# design.net
KiCad netlist of a schematic drawn in Altium Designer
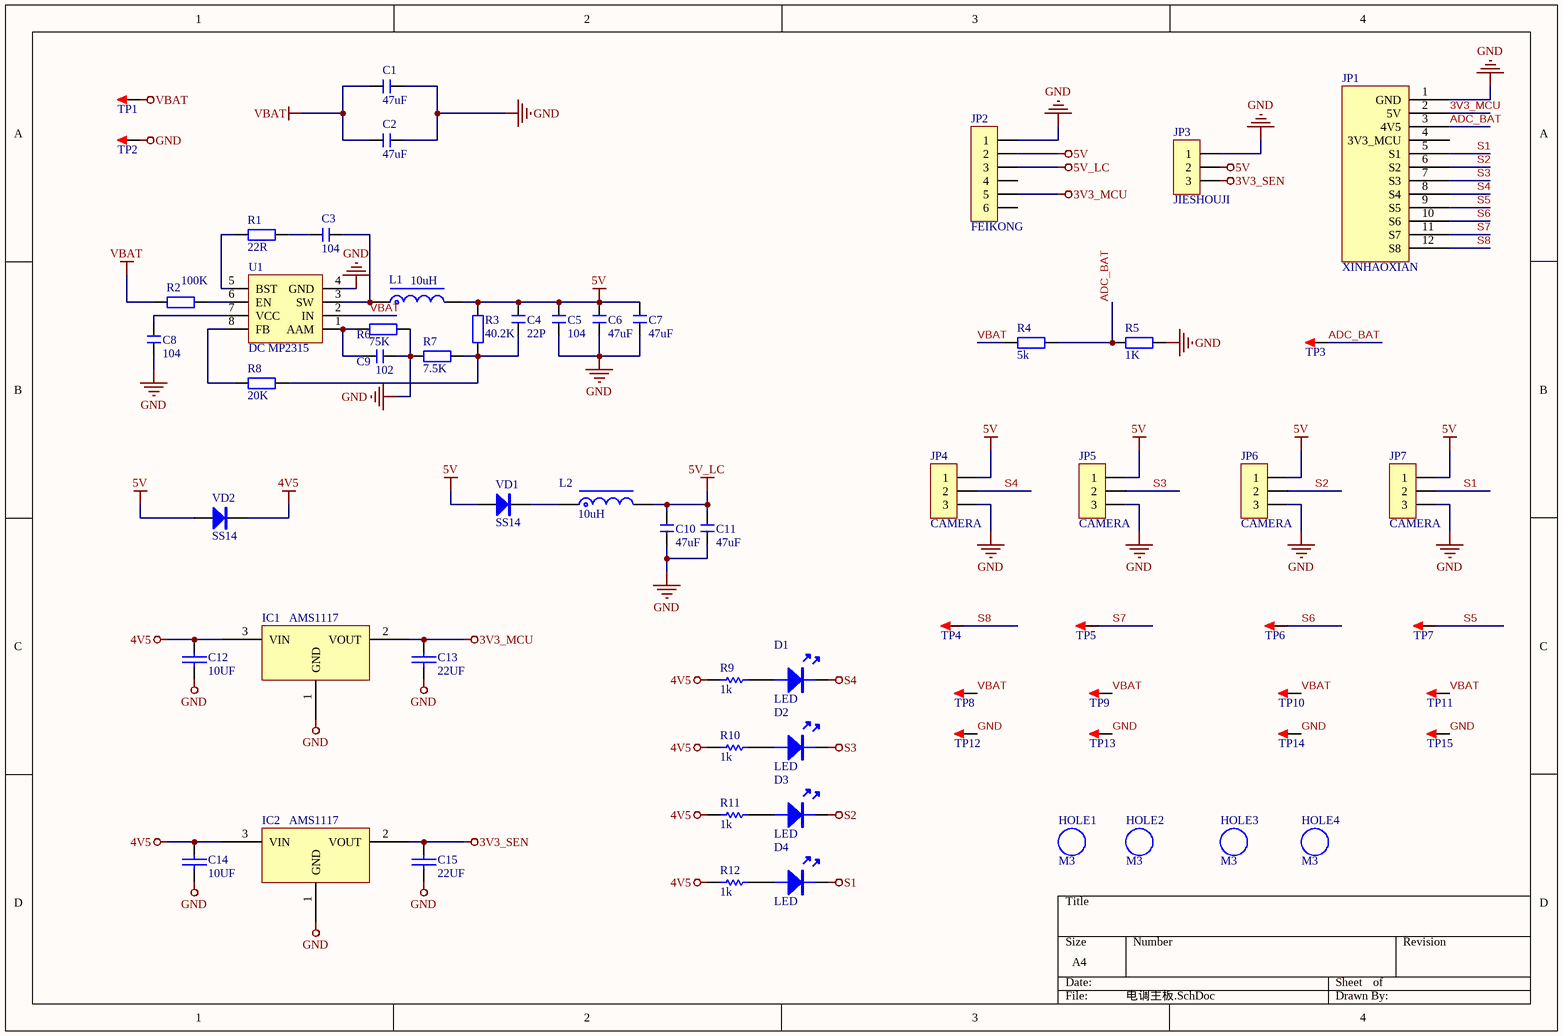
[diagram p0: 电调主板.SchDoc]

(export (version "E")
  (design (tool "Eeschema 10.0.6"))
  (components
    (comp (ref "C1")
      (value "47uF")
      (footprint "0603C")
      (description "无极性贴片电容")
      (fields (field (name "版权归属") "源创客"))
      (libsource (lib "ATKF405 V1.1") (part "C"))
    )
    (comp (ref "C2")
      (value "47uF")
      (footprint "0603C")
      (description "无极性贴片电容")
      (fields (field (name "版权归属") "源创客"))
      (libsource (lib "ATKF405 V1.1") (part "C"))
    )
    (comp (ref "C3")
      (value "104")
      (footprint "0603C")
      (description "无极性贴片电容")
      (fields (field (name "版权归属") "源创客"))
      (libsource (lib "ATKF405 V1.1") (part "C"))
    )
    (comp (ref "C4")
      (value "22P")
      (footprint "0603C")
      (description "无极性贴片电容")
      (fields (field (name "版权归属") "源创客"))
      (libsource (lib "ATKF405 V1.1") (part "C"))
    )
    (comp (ref "C5")
      (value "104")
      (footprint "0603C")
      (description "无极性贴片电容")
      (fields (field (name "版权归属") "源创客"))
      (libsource (lib "ATKF405 V1.1") (part "C"))
    )
    (comp (ref "C6")
      (value "47uF")
      (footprint "0603C")
      (description "无极性贴片电容")
      (fields (field (name "版权归属") "源创客"))
      (libsource (lib "ATKF405 V1.1") (part "C"))
    )
    (comp (ref "C7")
      (value "47uF")
      (footprint "0603C")
      (description "无极性贴片电容")
      (fields (field (name "版权归属") "源创客"))
      (libsource (lib "ATKF405 V1.1") (part "C"))
    )
    (comp (ref "C8")
      (value "104")
      (footprint "0603C")
      (description "无极性贴片电容")
      (fields (field (name "版权归属") "源创客"))
      (libsource (lib "ATKF405 V1.1") (part "C"))
    )
    (comp (ref "C9")
      (value "102")
      (footprint "0603C")
      (description "无极性贴片电容")
      (fields (field (name "版权归属") "源创客"))
      (libsource (lib "ATKF405 V1.1") (part "C"))
    )
    (comp (ref "C10")
      (value "47uF")
      (footprint "0603C")
      (description "无极性贴片电容")
      (fields (field (name "版权归属") "源创客"))
      (libsource (lib "ATKF405 V1.1") (part "C"))
    )
    (comp (ref "C11")
      (value "47uF")
      (footprint "0603C")
      (description "无极性贴片电容")
      (fields (field (name "版权归属") "源创客"))
      (libsource (lib "ATKF405 V1.1") (part "C"))
    )
    (comp (ref "C12")
      (value "10UF")
      (footprint "0603C")
      (description "无极性电容")
      (libsource (lib "电容") (part "CAP"))
    )
    (comp (ref "C13")
      (value "22UF")
      (footprint "0603C")
      (description "无极性电容")
      (libsource (lib "电容") (part "CAP"))
    )
    (comp (ref "C14")
      (value "10UF")
      (footprint "0603C")
      (description "无极性电容")
      (libsource (lib "电容") (part "CAP"))
    )
    (comp (ref "C15")
      (value "22UF")
      (footprint "0603C")
      (description "无极性电容")
      (libsource (lib "电容") (part "CAP"))
    )
    (comp (ref "D1") (value "LED") (footprint "LED-0603G") (libsource (lib "LED") (part "LED")))
    (comp (ref "D2") (value "LED") (footprint "LED-0603G") (libsource (lib "LED") (part "LED")))
    (comp (ref "D3") (value "LED") (footprint "LED-0603G") (libsource (lib "LED") (part "LED")))
    (comp (ref "D4") (value "LED") (footprint "LED-0603G") (libsource (lib "LED") (part "LED")))
    (comp (ref "HOLE1")
      (value "M3")
      (footprint "M3 5.4MM")
      (description "铜柱孔")
      (fields (field (name "版权归属") "源创客"))
      (libsource (lib "STM32F407_CORE_BOARD") (part "M3"))
    )
    (comp (ref "HOLE2")
      (value "M3")
      (footprint "M3 5.4MM")
      (description "铜柱孔")
      (fields (field (name "版权归属") "源创客"))
      (libsource (lib "STM32F407_CORE_BOARD") (part "M3"))
    )
    (comp (ref "HOLE3")
      (value "M3")
      (footprint "M3 5.4MM")
      (description "铜柱孔")
      (fields (field (name "版权归属") "源创客"))
      (libsource (lib "STM32F407_CORE_BOARD") (part "M3"))
    )
    (comp (ref "HOLE4")
      (value "M3")
      (footprint "M3 5.4MM")
      (description "铜柱孔")
      (fields (field (name "版权归属") "源创客"))
      (libsource (lib "STM32F407_CORE_BOARD") (part "M3"))
    )
    (comp (ref "IC1")
      (value "AMS1117")
      (footprint "AMS1117")
      (description "3V3降压芯片")
      (libsource (lib "飞控主板") (part "AMS1117"))
    )
    (comp (ref "IC2")
      (value "AMS1117")
      (footprint "AMS1117")
      (description "3V3降压芯片")
      (libsource (lib "飞控主板") (part "AMS1117"))
    )
    (comp (ref "JP1")
      (value "XINHAOXIAN")
      (footprint "Headr14")
      (description "14PIN接插件")
      (libsource (lib "飞控主板") (part "Header14"))
    )
    (comp (ref "JP2")
      (value "FEIKONG")
      (footprint "SH1.0 S-W-6P")
      (description "6P接插件")
      (fields (field (name "版权归属") "源创客"))
      (libsource (lib "ATKF405 V1.1") (part "Header 6"))
    )
    (comp (ref "JP3")
      (value "JIESHOUJI")
      (footprint "MX 1.25-WS-3P")
      (description "3P接插件")
      (fields (field (name "版权归属") "源创客"))
      (libsource (lib "ATKF405 V1.1") (part "Header 3"))
    )
    (comp (ref "JP4")
      (value "CAMERA")
      (footprint "MX 1.25-WS-3P")
      (description "3P接插件")
      (fields (field (name "版权归属") "源创客"))
      (libsource (lib "ATKF405 V1.1") (part "Header 3"))
    )
    (comp (ref "JP5")
      (value "CAMERA")
      (footprint "MX 1.25-WS-3P")
      (description "3P接插件")
      (fields (field (name "版权归属") "源创客"))
      (libsource (lib "ATKF405 V1.1") (part "Header 3"))
    )
    (comp (ref "JP6")
      (value "CAMERA")
      (footprint "MX 1.25-WS-3P")
      (description "3P接插件")
      (fields (field (name "版权归属") "源创客"))
      (libsource (lib "ATKF405 V1.1") (part "Header 3"))
    )
    (comp (ref "JP7")
      (value "CAMERA")
      (footprint "MX 1.25-WS-3P")
      (description "3P接插件")
      (fields (field (name "版权归属") "源创客"))
      (libsource (lib "ATKF405 V1.1") (part "Header 3"))
    )
    (comp (ref "L1")
      (value "10uH")
      (footprint "L-SMD-0420")
      (description "功率屏蔽电感")
      (fields (field (name "版权归属") "源创客"))
      (libsource (lib "ATKF405 V1.1") (part "L-CDRH"))
    )
    (comp (ref "L2")
      (value "10uH")
      (footprint "NR3015")
      (description "NR功率电感")
      (fields (field (name "版权归属") "源创客"))
      (libsource (lib "ATKF405 V1.1") (part "L-NR"))
    )
    (comp (ref "R1")
      (value "22R")
      (footprint "0805R")
      (description "贴片电阻")
      (fields (field (name "版权归属") "源创客"))
      (libsource (lib "ATKF405 V1.1") (part "R"))
    )
    (comp (ref "R2")
      (value "100K")
      (footprint "0805R")
      (description "贴片电阻")
      (fields (field (name "版权归属") "源创客"))
      (libsource (lib "ATKF405 V1.1") (part "R"))
    )
    (comp (ref "R3")
      (value "40.2K")
      (footprint "0805R")
      (description "贴片电阻")
      (fields (field (name "版权归属") "源创客"))
      (libsource (lib "ATKF405 V1.1") (part "R"))
    )
    (comp (ref "R4")
      (value "5k")
      (footprint "0805R")
      (description "贴片电阻")
      (fields (field (name "版权归属") "源创客"))
      (libsource (lib "ATKF405 V1.1") (part "R"))
    )
    (comp (ref "R5")
      (value "1K")
      (footprint "0805R")
      (description "贴片电阻")
      (fields (field (name "版权归属") "源创客"))
      (libsource (lib "ATKF405 V1.1") (part "R"))
    )
    (comp (ref "R6")
      (value "75K")
      (footprint "0805R")
      (description "贴片电阻")
      (fields (field (name "版权归属") "源创客"))
      (libsource (lib "ATKF405 V1.1") (part "R"))
    )
    (comp (ref "R7")
      (value "7.5K")
      (footprint "0805R")
      (description "贴片电阻")
      (fields (field (name "版权归属") "源创客"))
      (libsource (lib "ATKF405 V1.1") (part "R"))
    )
    (comp (ref "R8")
      (value "20K")
      (footprint "0805R")
      (description "贴片电阻")
      (fields (field (name "版权归属") "源创客"))
      (libsource (lib "ATKF405 V1.1") (part "R"))
    )
    (comp (ref "R9") (value "1k") (footprint "0805R") (libsource (lib "电阻") (part "RES")))
    (comp (ref "R10") (value "1k") (footprint "0805R") (libsource (lib "电阻") (part "RES")))
    (comp (ref "R11") (value "1k") (footprint "0805R") (libsource (lib "电阻") (part "RES")))
    (comp (ref "R12") (value "1k") (footprint "0805R") (libsource (lib "电阻") (part "RES")))
    (comp (ref "TP1")
      (value "TEST")
      (footprint "TEST PAD 1.8")
      (description "测试点")
      (fields (field (name "版权归属") "源创客"))
      (libsource (lib "ATKF405 V1.1") (part "TEST"))
    )
    (comp (ref "TP2")
      (value "TEST")
      (footprint "TEST PAD 1.8")
      (description "测试点")
      (fields (field (name "版权归属") "源创客"))
      (libsource (lib "ATKF405 V1.1") (part "TEST"))
    )
    (comp (ref "TP3")
      (value "TEST")
      (footprint "TEST PAD 1.8")
      (description "测试点")
      (fields (field (name "版权归属") "源创客"))
      (libsource (lib "ATKF405 V1.1") (part "TEST"))
    )
    (comp (ref "TP4")
      (value "TEST")
      (footprint "TEST PAD 1.8")
      (description "测试点")
      (fields (field (name "版权归属") "源创客"))
      (libsource (lib "ATKF405 V1.1") (part "TEST"))
    )
    (comp (ref "TP5")
      (value "TEST")
      (footprint "TEST PAD 1.8")
      (description "测试点")
      (fields (field (name "版权归属") "源创客"))
      (libsource (lib "ATKF405 V1.1") (part "TEST"))
    )
    (comp (ref "TP6")
      (value "TEST")
      (footprint "TEST PAD 1.8")
      (description "测试点")
      (fields (field (name "版权归属") "源创客"))
      (libsource (lib "ATKF405 V1.1") (part "TEST"))
    )
    (comp (ref "TP7")
      (value "TEST")
      (footprint "TEST PAD 1.8")
      (description "测试点")
      (fields (field (name "版权归属") "源创客"))
      (libsource (lib "ATKF405 V1.1") (part "TEST"))
    )
    (comp (ref "TP8")
      (value "TEST")
      (footprint "TEST PAD 1.8")
      (description "测试点")
      (fields (field (name "版权归属") "源创客"))
      (libsource (lib "ATKF405 V1.1") (part "TEST"))
    )
    (comp (ref "TP9")
      (value "TEST")
      (footprint "TEST PAD 1.8")
      (description "测试点")
      (fields (field (name "版权归属") "源创客"))
      (libsource (lib "ATKF405 V1.1") (part "TEST"))
    )
    (comp (ref "TP10")
      (value "TEST")
      (footprint "TEST PAD 1.8")
      (description "测试点")
      (fields (field (name "版权归属") "源创客"))
      (libsource (lib "ATKF405 V1.1") (part "TEST"))
    )
    (comp (ref "TP11")
      (value "TEST")
      (footprint "TEST PAD 1.8")
      (description "测试点")
      (fields (field (name "版权归属") "源创客"))
      (libsource (lib "ATKF405 V1.1") (part "TEST"))
    )
    (comp (ref "TP12")
      (value "TEST")
      (footprint "TEST PAD 1.8")
      (description "测试点")
      (fields (field (name "版权归属") "源创客"))
      (libsource (lib "ATKF405 V1.1") (part "TEST"))
    )
    (comp (ref "TP13")
      (value "TEST")
      (footprint "TEST PAD 1.8")
      (description "测试点")
      (fields (field (name "版权归属") "源创客"))
      (libsource (lib "ATKF405 V1.1") (part "TEST"))
    )
    (comp (ref "TP14")
      (value "TEST")
      (footprint "TEST PAD 1.8")
      (description "测试点")
      (fields (field (name "版权归属") "源创客"))
      (libsource (lib "ATKF405 V1.1") (part "TEST"))
    )
    (comp (ref "TP15")
      (value "TEST")
      (footprint "TEST PAD 1.8")
      (description "测试点")
      (fields (field (name "版权归属") "源创客"))
      (libsource (lib "ATKF405 V1.1") (part "TEST"))
    )
    (comp (ref "U1")
      (value "DC MP2315")
      (footprint "SOT23-8L")
      (description "DC降压芯片")
      (libsource (lib "ATKF405 V1.1") (part "DC MP2315"))
    )
    (comp (ref "VD1")
      (value "SS14")
      (footprint "SOD-123")
      (description "肖特基二极管")
      (fields (field (name "版权归属") "源创客"))
      (libsource (lib "ATKF405 V1.1") (part "SS14"))
    )
    (comp (ref "VD2")
      (value "SS14")
      (footprint "SOD-123")
      (description "肖特基二极管")
      (fields (field (name "版权归属") "源创客"))
      (libsource (lib "ATKF405 V1.1") (part "SS14"))
    )
  )
  (nets
    (net (code "1") (name "/ADC_BAT") (class "Default")
      (node (ref "JP1") (pin "3") (pinfunction "4V5_3") (pintype "passive"))
      (node (ref "R4") (pin "1") (pinfunction "1_1") (pintype "passive"))
      (node (ref "R5") (pin "2") (pinfunction "2_2") (pintype "passive"))
      (node (ref "TP3") (pin "1") (pinfunction "1_1") (pintype "passive"))
    )
    (net (code "2") (name "/S5") (class "Default")
      (node (ref "JP1") (pin "9") (pinfunction "S5_9") (pintype "passive"))
      (node (ref "TP7") (pin "1") (pinfunction "1_1") (pintype "passive"))
    )
    (net (code "3") (name "/S6") (class "Default")
      (node (ref "JP1") (pin "10") (pinfunction "S6_10") (pintype "passive"))
      (node (ref "TP6") (pin "1") (pinfunction "1_1") (pintype "passive"))
    )
    (net (code "4") (name "/S7") (class "Default")
      (node (ref "JP1") (pin "11") (pinfunction "S7_11") (pintype "passive"))
      (node (ref "TP5") (pin "1") (pinfunction "1_1") (pintype "passive"))
    )
    (net (code "5") (name "/S8") (class "Default")
      (node (ref "JP1") (pin "12") (pinfunction "S8_12") (pintype "passive"))
      (node (ref "TP4") (pin "1") (pinfunction "1_1") (pintype "passive"))
    )
    (net (code "6") (name "3V3_MCU") (class "Default")
      (node (ref "C13") (pin "2") (pinfunction "2_2") (pintype "passive"))
      (node (ref "IC1") (pin "2") (pinfunction "VOUT_2") (pintype "passive"))
      (node (ref "JP1") (pin "2") (pinfunction "5V_2") (pintype "passive"))
      (node (ref "JP2") (pin "5") (pinfunction "5_5") (pintype "passive"))
    )
    (net (code "7") (name "3V3_SEN") (class "Default")
      (node (ref "C15") (pin "2") (pinfunction "2_2") (pintype "passive"))
      (node (ref "IC2") (pin "2") (pinfunction "VOUT_2") (pintype "passive"))
      (node (ref "JP3") (pin "3") (pinfunction "3_3") (pintype "passive"))
    )
    (net (code "8") (name "4V5") (class "Default")
      (node (ref "C12") (pin "2") (pinfunction "2_2") (pintype "passive"))
      (node (ref "C14") (pin "2") (pinfunction "2_2") (pintype "passive"))
      (node (ref "IC1") (pin "3") (pinfunction "VIN_3") (pintype "passive"))
      (node (ref "IC2") (pin "3") (pinfunction "VIN_3") (pintype "passive"))
      (node (ref "R10") (pin "1") (pinfunction "1_1") (pintype "passive"))
      (node (ref "R11") (pin "1") (pinfunction "1_1") (pintype "passive"))
      (node (ref "R12") (pin "1") (pinfunction "1_1") (pintype "passive"))
      (node (ref "R9") (pin "1") (pinfunction "1_1") (pintype "passive"))
      (node (ref "VD2") (pin "2") (pinfunction "K_2") (pintype "passive"))
    )
    (net (code "9") (name "5V") (class "Default")
      (node (ref "C4") (pin "1") (pinfunction "1_1") (pintype "passive"))
      (node (ref "C5") (pin "1") (pinfunction "1_1") (pintype "passive"))
      (node (ref "C6") (pin "1") (pinfunction "1_1") (pintype "passive"))
      (node (ref "C7") (pin "1") (pinfunction "1_1") (pintype "passive"))
      (node (ref "JP2") (pin "2") (pinfunction "2_2") (pintype "passive"))
      (node (ref "JP3") (pin "2") (pinfunction "2_2") (pintype "passive"))
      (node (ref "JP4") (pin "1") (pinfunction "1_1") (pintype "passive"))
      (node (ref "JP5") (pin "1") (pinfunction "1_1") (pintype "passive"))
      (node (ref "JP6") (pin "1") (pinfunction "1_1") (pintype "passive"))
      (node (ref "JP7") (pin "1") (pinfunction "1_1") (pintype "passive"))
      (node (ref "L1") (pin "2") (pinfunction "2_2") (pintype "passive"))
      (node (ref "R3") (pin "2") (pinfunction "2_2") (pintype "passive"))
      (node (ref "VD1") (pin "1") (pinfunction "A_1") (pintype "passive"))
      (node (ref "VD2") (pin "1") (pinfunction "A_1") (pintype "passive"))
    )
    (net (code "10") (name "5V_LC") (class "Default")
      (node (ref "C10") (pin "2") (pinfunction "2_2") (pintype "passive"))
      (node (ref "C11") (pin "2") (pinfunction "2_2") (pintype "passive"))
      (node (ref "JP2") (pin "3") (pinfunction "3_3") (pintype "passive"))
      (node (ref "L2") (pin "2") (pinfunction "2_2") (pintype "passive"))
    )
    (net (code "11") (name "GND") (class "Default")
      (node (ref "C1") (pin "1") (pinfunction "1_1") (pintype "passive"))
      (node (ref "C10") (pin "1") (pinfunction "1_1") (pintype "passive"))
      (node (ref "C11") (pin "1") (pinfunction "1_1") (pintype "passive"))
      (node (ref "C12") (pin "1") (pinfunction "1_1") (pintype "passive"))
      (node (ref "C13") (pin "1") (pinfunction "1_1") (pintype "passive"))
      (node (ref "C14") (pin "1") (pinfunction "1_1") (pintype "passive"))
      (node (ref "C15") (pin "1") (pinfunction "1_1") (pintype "passive"))
      (node (ref "C2") (pin "1") (pinfunction "1_1") (pintype "passive"))
      (node (ref "C5") (pin "2") (pinfunction "2_2") (pintype "passive"))
      (node (ref "C6") (pin "2") (pinfunction "2_2") (pintype "passive"))
      (node (ref "C7") (pin "2") (pinfunction "2_2") (pintype "passive"))
      (node (ref "C8") (pin "1") (pinfunction "1_1") (pintype "passive"))
      (node (ref "C9") (pin "1") (pinfunction "1_1") (pintype "passive"))
      (node (ref "IC1") (pin "1") (pinfunction "GND_1") (pintype "passive"))
      (node (ref "IC2") (pin "1") (pinfunction "GND_1") (pintype "passive"))
      (node (ref "JP1") (pin "1") (pinfunction "GND_1") (pintype "passive"))
      (node (ref "JP2") (pin "1") (pinfunction "1_1") (pintype "passive"))
      (node (ref "JP3") (pin "1") (pinfunction "1_1") (pintype "passive"))
      (node (ref "JP4") (pin "3") (pinfunction "3_3") (pintype "passive"))
      (node (ref "JP5") (pin "3") (pinfunction "3_3") (pintype "passive"))
      (node (ref "JP6") (pin "3") (pinfunction "3_3") (pintype "passive"))
      (node (ref "JP7") (pin "3") (pinfunction "3_3") (pintype "passive"))
      (node (ref "R5") (pin "1") (pinfunction "1_1") (pintype "passive"))
      (node (ref "R6") (pin "2") (pinfunction "2_2") (pintype "passive"))
      (node (ref "R7") (pin "1") (pinfunction "1_1") (pintype "passive"))
      (node (ref "TP12") (pin "1") (pinfunction "1_1") (pintype "passive"))
      (node (ref "TP13") (pin "1") (pinfunction "1_1") (pintype "passive"))
      (node (ref "TP14") (pin "1") (pinfunction "1_1") (pintype "passive"))
      (node (ref "TP15") (pin "1") (pinfunction "1_1") (pintype "passive"))
      (node (ref "TP2") (pin "1") (pinfunction "1_1") (pintype "passive"))
      (node (ref "U1") (pin "4") (pinfunction "GND_4") (pintype "passive"))
    )
    (net (code "12") (name "Net-(C3-Pad2)") (class "Default")
      (node (ref "C3") (pin "2") (pinfunction "2_2") (pintype "passive"))
      (node (ref "R1") (pin "2") (pinfunction "2_2") (pintype "passive"))
    )
    (net (code "13") (name "Net-(C4-Pad2)") (class "Default")
      (node (ref "C4") (pin "2") (pinfunction "2_2") (pintype "passive"))
      (node (ref "R3") (pin "1") (pinfunction "1_1") (pintype "passive"))
      (node (ref "R7") (pin "2") (pinfunction "2_2") (pintype "passive"))
      (node (ref "R8") (pin "2") (pinfunction "2_2") (pintype "passive"))
    )
    (net (code "14") (name "Net-(D1-PadA)") (class "Default")
      (node (ref "D1") (pin "A") (pinfunction "A_A") (pintype "passive"))
      (node (ref "R9") (pin "2") (pinfunction "2_2") (pintype "passive"))
    )
    (net (code "15") (name "Net-(D2-PadA)") (class "Default")
      (node (ref "D2") (pin "A") (pinfunction "A_A") (pintype "passive"))
      (node (ref "R10") (pin "2") (pinfunction "2_2") (pintype "passive"))
    )
    (net (code "16") (name "Net-(D3-PadA)") (class "Default")
      (node (ref "D3") (pin "A") (pinfunction "A_A") (pintype "passive"))
      (node (ref "R11") (pin "2") (pinfunction "2_2") (pintype "passive"))
    )
    (net (code "17") (name "Net-(D4-PadA)") (class "Default")
      (node (ref "D4") (pin "A") (pinfunction "A_A") (pintype "passive"))
      (node (ref "R12") (pin "2") (pinfunction "2_2") (pintype "passive"))
    )
    (net (code "18") (name "Net-(U1-AAM)") (class "Default")
      (node (ref "C9") (pin "2") (pinfunction "2_2") (pintype "passive"))
      (node (ref "R6") (pin "1") (pinfunction "1_1") (pintype "passive"))
      (node (ref "U1") (pin "1") (pinfunction "AAM_1") (pintype "passive"))
    )
    (net (code "19") (name "Net-(U1-BST)") (class "Default")
      (node (ref "R1") (pin "1") (pinfunction "1_1") (pintype "passive"))
      (node (ref "U1") (pin "5") (pinfunction "BST_5") (pintype "passive"))
    )
    (net (code "20") (name "Net-(U1-EN)") (class "Default")
      (node (ref "R2") (pin "2") (pinfunction "2_2") (pintype "passive"))
      (node (ref "U1") (pin "6") (pinfunction "EN_6") (pintype "passive"))
    )
    (net (code "21") (name "Net-(U1-FB)") (class "Default")
      (node (ref "R8") (pin "1") (pinfunction "1_1") (pintype "passive"))
      (node (ref "U1") (pin "8") (pinfunction "FB_8") (pintype "passive"))
    )
    (net (code "22") (name "Net-(U1-SW)") (class "Default")
      (node (ref "C3") (pin "1") (pinfunction "1_1") (pintype "passive"))
      (node (ref "L1") (pin "1") (pinfunction "1_1") (pintype "passive"))
      (node (ref "U1") (pin "3") (pinfunction "SW_3") (pintype "passive"))
    )
    (net (code "23") (name "Net-(U1-VCC)") (class "Default")
      (node (ref "C8") (pin "2") (pinfunction "2_2") (pintype "passive"))
      (node (ref "U1") (pin "7") (pinfunction "VCC_7") (pintype "passive"))
    )
    (net (code "24") (name "Net-(VD1-K)") (class "Default")
      (node (ref "L2") (pin "1") (pinfunction "1_1") (pintype "passive"))
      (node (ref "VD1") (pin "2") (pinfunction "K_2") (pintype "passive"))
    )
    (net (code "25") (name "S1") (class "Default")
      (node (ref "D4") (pin "K") (pinfunction "K_K") (pintype "passive"))
      (node (ref "JP1") (pin "5") (pinfunction "S1_5") (pintype "passive"))
      (node (ref "JP7") (pin "2") (pinfunction "2_2") (pintype "passive"))
    )
    (net (code "26") (name "S2") (class "Default")
      (node (ref "D3") (pin "K") (pinfunction "K_K") (pintype "passive"))
      (node (ref "JP1") (pin "6") (pinfunction "S2_6") (pintype "passive"))
      (node (ref "JP6") (pin "2") (pinfunction "2_2") (pintype "passive"))
    )
    (net (code "27") (name "S3") (class "Default")
      (node (ref "D2") (pin "K") (pinfunction "K_K") (pintype "passive"))
      (node (ref "JP1") (pin "7") (pinfunction "S3_7") (pintype "passive"))
      (node (ref "JP5") (pin "2") (pinfunction "2_2") (pintype "passive"))
    )
    (net (code "28") (name "S4") (class "Default")
      (node (ref "D1") (pin "K") (pinfunction "K_K") (pintype "passive"))
      (node (ref "JP1") (pin "8") (pinfunction "S4_8") (pintype "passive"))
      (node (ref "JP4") (pin "2") (pinfunction "2_2") (pintype "passive"))
    )
    (net (code "29") (name "VBAT") (class "Default")
      (node (ref "C1") (pin "2") (pinfunction "2_2") (pintype "passive"))
      (node (ref "C2") (pin "2") (pinfunction "2_2") (pintype "passive"))
      (node (ref "R2") (pin "1") (pinfunction "1_1") (pintype "passive"))
      (node (ref "R4") (pin "2") (pinfunction "2_2") (pintype "passive"))
      (node (ref "TP1") (pin "1") (pinfunction "1_1") (pintype "passive"))
      (node (ref "TP10") (pin "1") (pinfunction "1_1") (pintype "passive"))
      (node (ref "TP11") (pin "1") (pinfunction "1_1") (pintype "passive"))
      (node (ref "TP8") (pin "1") (pinfunction "1_1") (pintype "passive"))
      (node (ref "TP9") (pin "1") (pinfunction "1_1") (pintype "passive"))
      (node (ref "U1") (pin "2") (pinfunction "IN_2") (pintype "passive"))
    )
    (net (code "30") (name "unconnected-(JP1-3V3_MCU-Pad4)") (class "Default")
      (node (ref "JP1") (pin "4") (pinfunction "3V3_MCU_4") (pintype "passive"))
    )
    (net (code "31") (name "unconnected-(JP2-Pad4)") (class "Default")
      (node (ref "JP2") (pin "4") (pinfunction "4_4") (pintype "passive"))
    )
    (net (code "32") (name "unconnected-(JP2-Pad6)") (class "Default")
      (node (ref "JP2") (pin "6") (pinfunction "6_6") (pintype "passive"))
    )
  )
)
